# badge_Rev_B.net
KiCad netlist of a schematic drawn in EAGLE
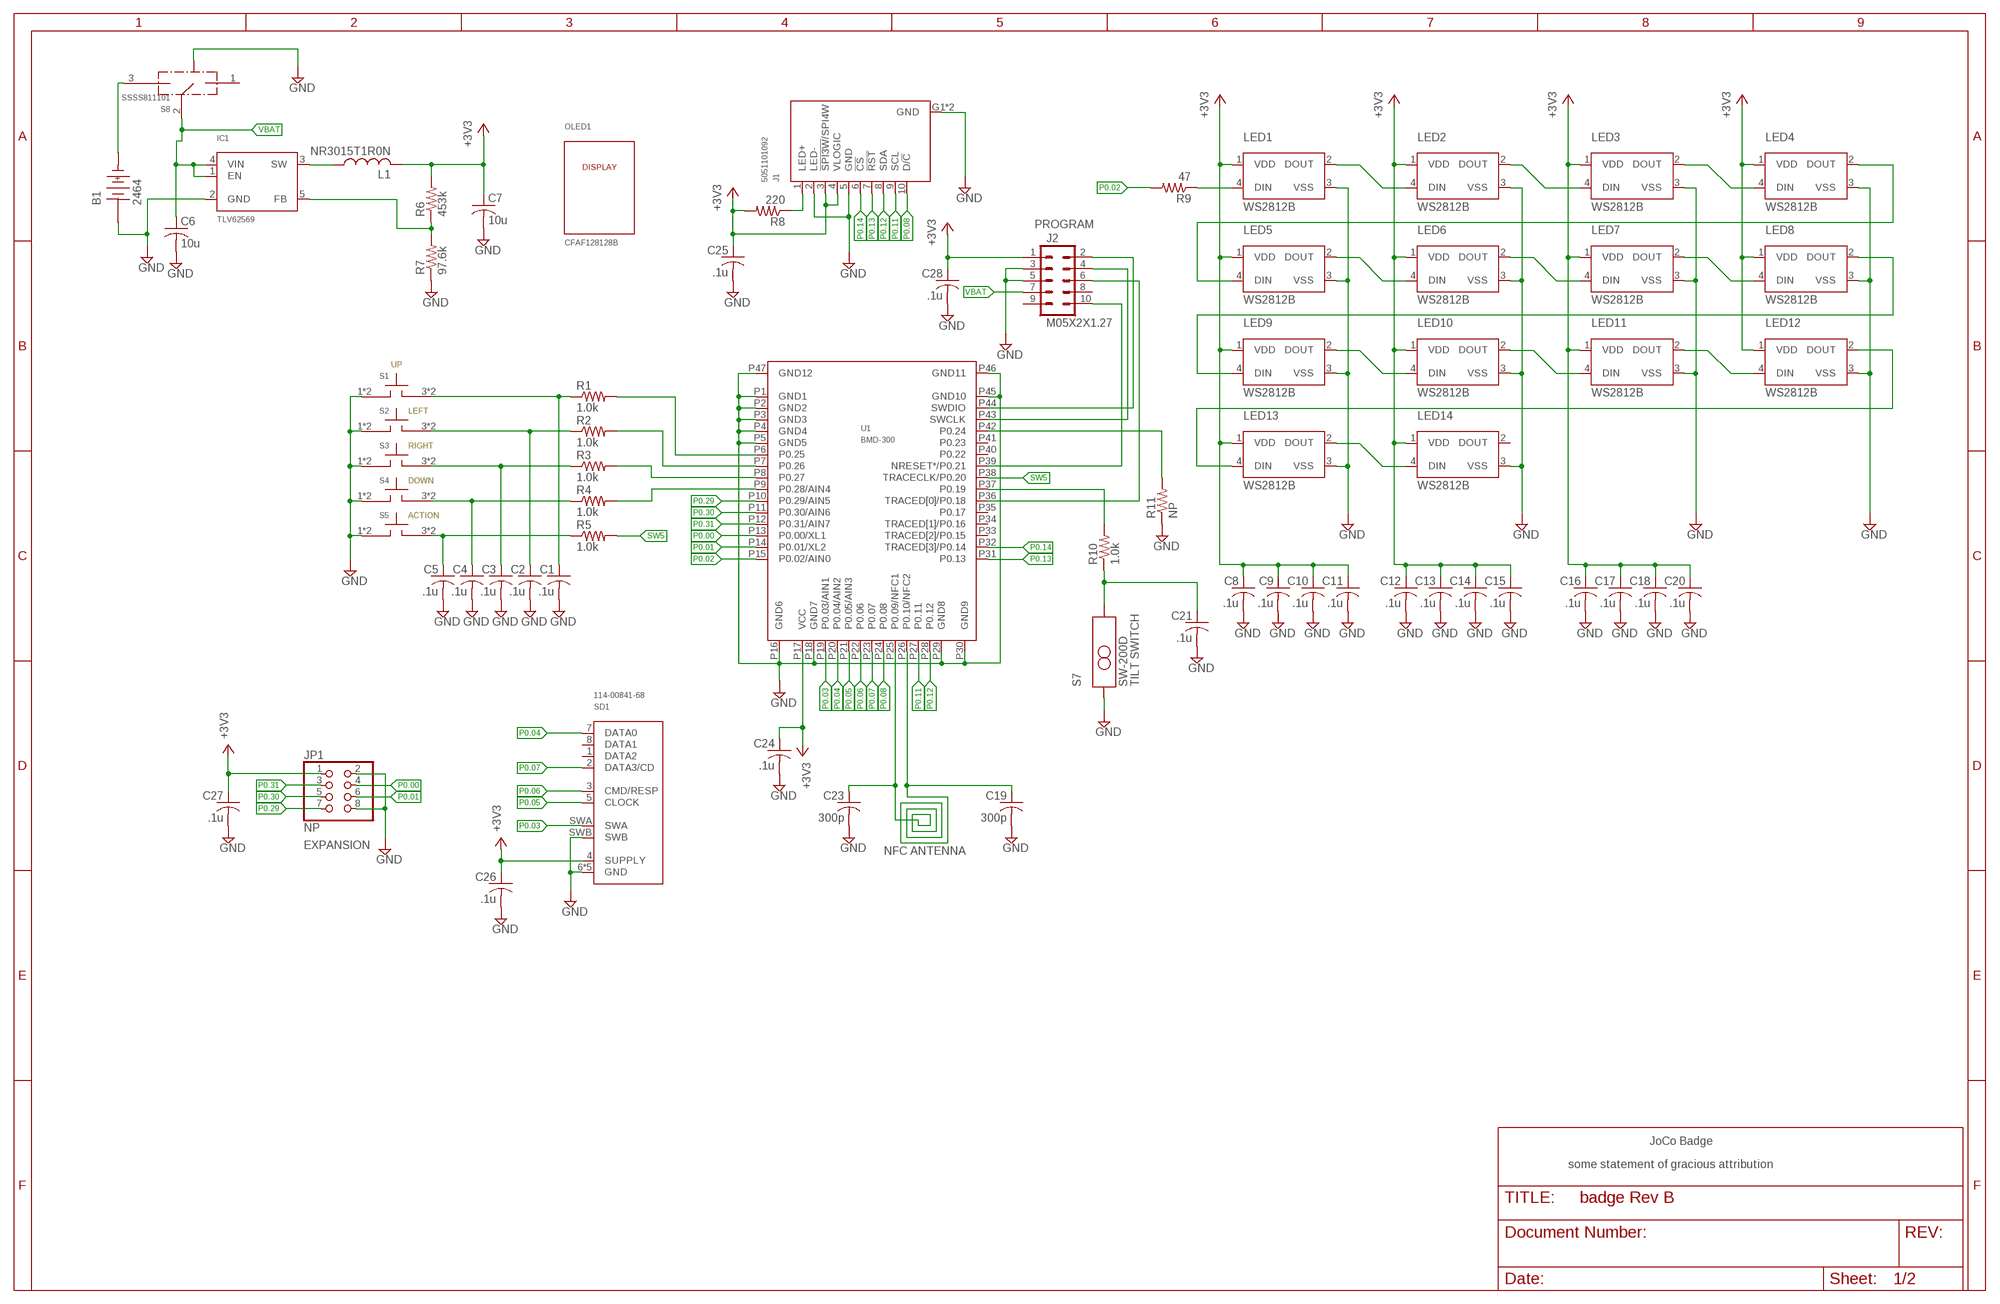
[diagram p0: schematic, sheet 1]
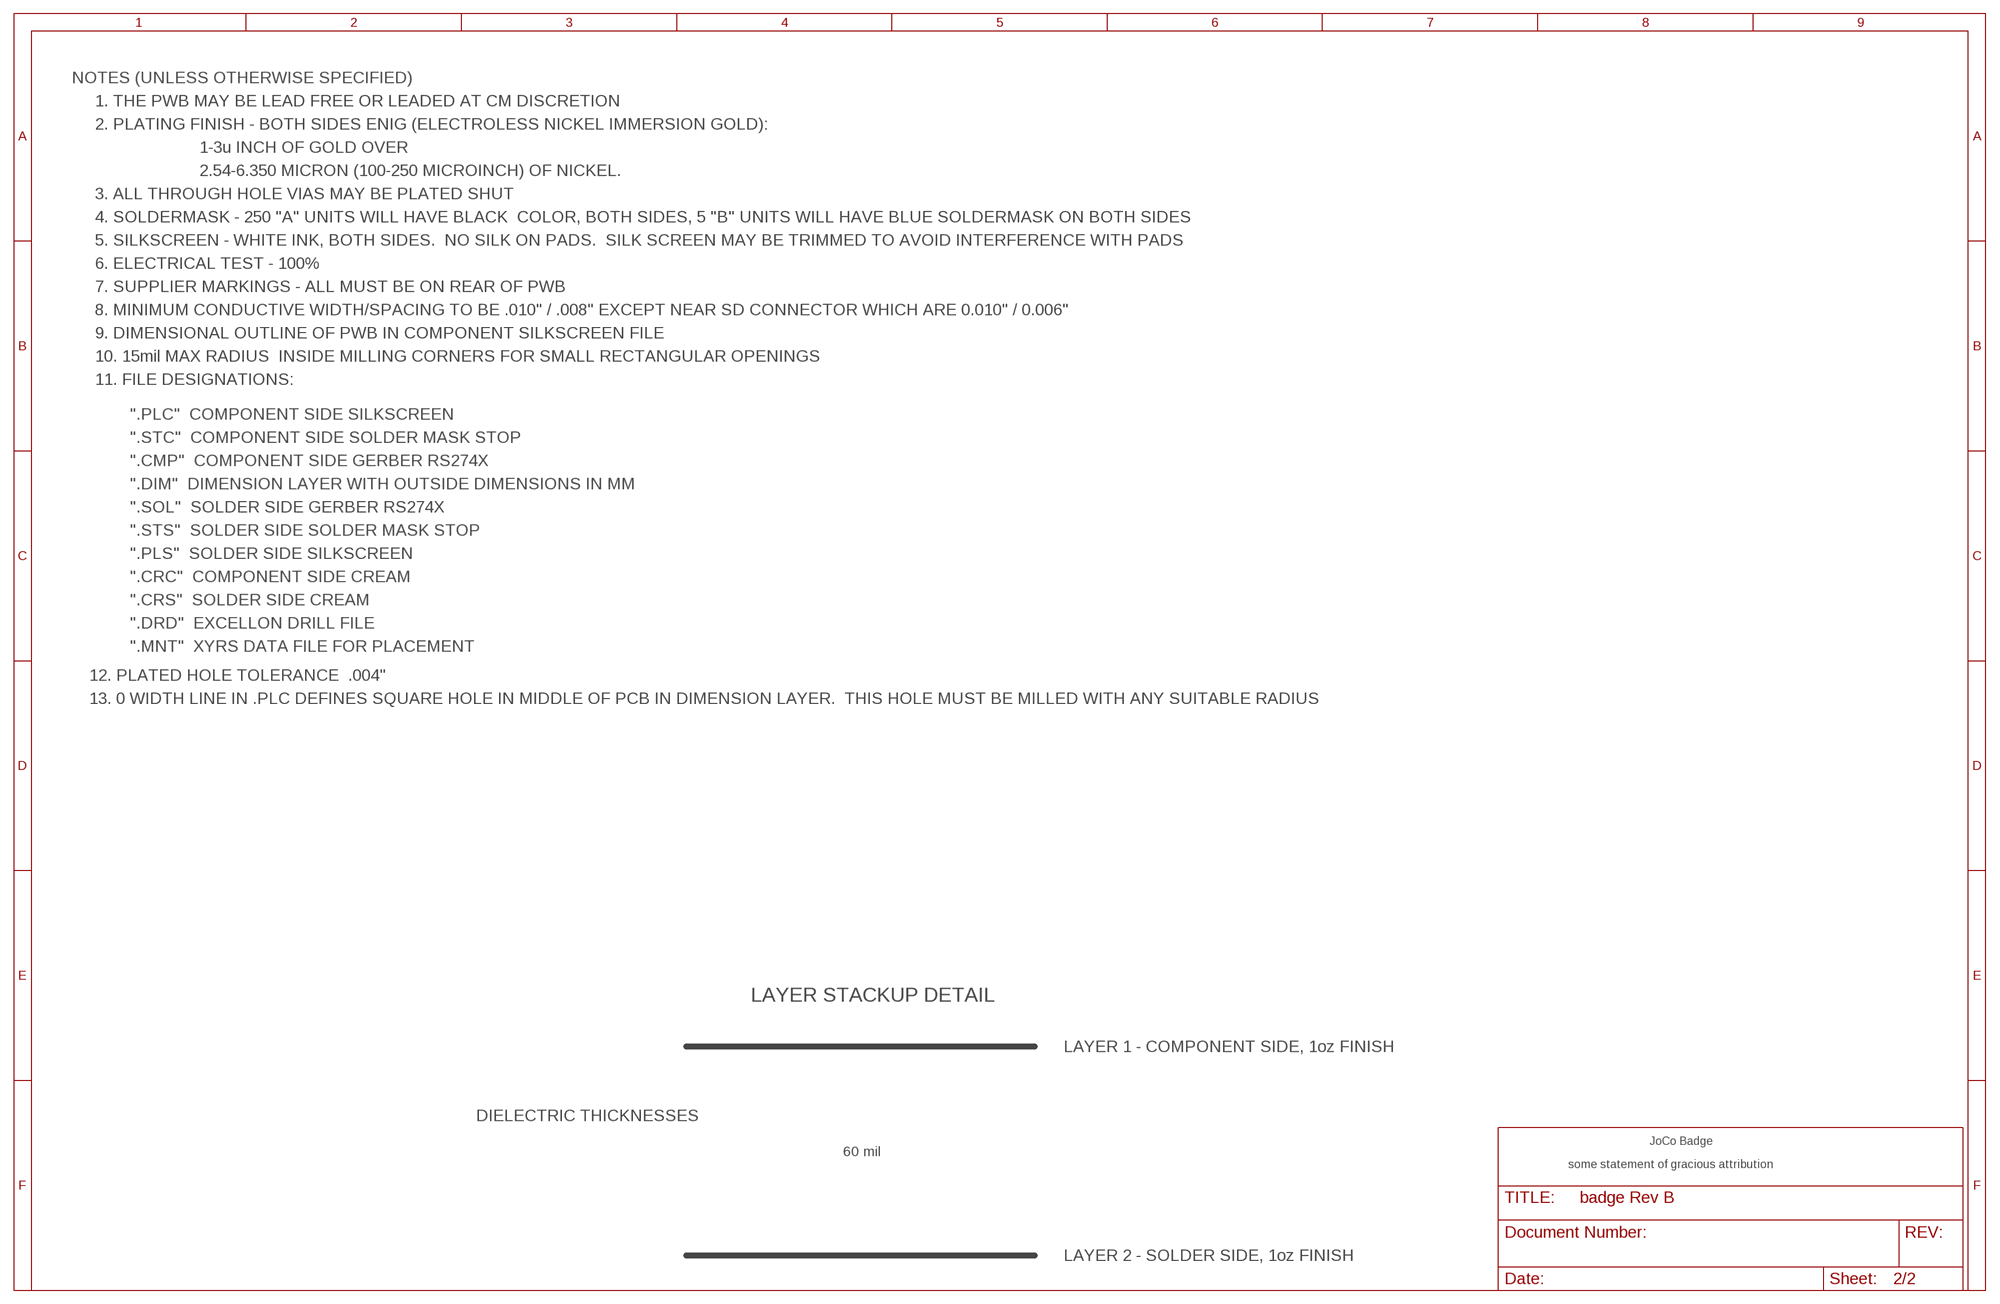
[diagram p1: schematic, sheet 2]

(export (version "E")
  (design (tool "Eeschema 10.0.6"))
  (components
    (comp (ref "B1")
      (value "2464")
      (footprint "eagle-import:2464")
      (libsource (lib "eagle-import") (part "2464"))
    )
    (comp (ref "C1")
      (value ".1u")
      (footprint "eagle-import:C0402K")
      (libsource (lib "eagle-import") (part "C-USC0402K"))
    )
    (comp (ref "C2")
      (value ".1u")
      (footprint "eagle-import:C0402K")
      (libsource (lib "eagle-import") (part "C-USC0402K"))
    )
    (comp (ref "C3")
      (value ".1u")
      (footprint "eagle-import:C0402K")
      (libsource (lib "eagle-import") (part "C-USC0402K"))
    )
    (comp (ref "C4")
      (value ".1u")
      (footprint "eagle-import:C0402K")
      (libsource (lib "eagle-import") (part "C-USC0402K"))
    )
    (comp (ref "C5")
      (value ".1u")
      (footprint "eagle-import:C0402K")
      (libsource (lib "eagle-import") (part "C-USC0402K"))
    )
    (comp (ref "C6")
      (value "10u")
      (footprint "eagle-import:C0805K")
      (fields (field (name "MPN") "JMK212BJ106KD-T"))
      (libsource (lib "eagle-import") (part "C-USC0805K"))
    )
    (comp (ref "C7")
      (value "10u")
      (footprint "eagle-import:C0805K")
      (fields (field (name "MPN") "JMK212BJ106KD-T"))
      (libsource (lib "eagle-import") (part "C-USC0805K"))
    )
    (comp (ref "C8")
      (value ".1u")
      (footprint "eagle-import:C0402K")
      (libsource (lib "eagle-import") (part "C-USC0402K"))
    )
    (comp (ref "C9")
      (value ".1u")
      (footprint "eagle-import:C0402K")
      (libsource (lib "eagle-import") (part "C-USC0402K"))
    )
    (comp (ref "C10")
      (value ".1u")
      (footprint "eagle-import:C0402K")
      (libsource (lib "eagle-import") (part "C-USC0402K"))
    )
    (comp (ref "C11")
      (value ".1u")
      (footprint "eagle-import:C0402K")
      (libsource (lib "eagle-import") (part "C-USC0402K"))
    )
    (comp (ref "C12")
      (value ".1u")
      (footprint "eagle-import:C0402K")
      (libsource (lib "eagle-import") (part "C-USC0402K"))
    )
    (comp (ref "C13")
      (value ".1u")
      (footprint "eagle-import:C0402K")
      (libsource (lib "eagle-import") (part "C-USC0402K"))
    )
    (comp (ref "C14")
      (value ".1u")
      (footprint "eagle-import:C0402K")
      (libsource (lib "eagle-import") (part "C-USC0402K"))
    )
    (comp (ref "C15")
      (value ".1u")
      (footprint "eagle-import:C0402K")
      (libsource (lib "eagle-import") (part "C-USC0402K"))
    )
    (comp (ref "C16")
      (value ".1u")
      (footprint "eagle-import:C0402K")
      (libsource (lib "eagle-import") (part "C-USC0402K"))
    )
    (comp (ref "C17")
      (value ".1u")
      (footprint "eagle-import:C0402K")
      (libsource (lib "eagle-import") (part "C-USC0402K"))
    )
    (comp (ref "C18")
      (value ".1u")
      (footprint "eagle-import:C0402K")
      (libsource (lib "eagle-import") (part "C-USC0402K"))
    )
    (comp (ref "C19")
      (value "300p")
      (footprint "eagle-import:C0603K")
      (libsource (lib "eagle-import") (part "C-USC0603K"))
    )
    (comp (ref "C20")
      (value ".1u")
      (footprint "eagle-import:C0402K")
      (libsource (lib "eagle-import") (part "C-USC0402K"))
    )
    (comp (ref "C21")
      (value ".1u")
      (footprint "eagle-import:C0402K")
      (libsource (lib "eagle-import") (part "C-USC0402K"))
    )
    (comp (ref "C23")
      (value "300p")
      (footprint "eagle-import:C0603K")
      (libsource (lib "eagle-import") (part "C-USC0603K"))
    )
    (comp (ref "C24")
      (value ".1u")
      (footprint "eagle-import:C0402K")
      (libsource (lib "eagle-import") (part "C-USC0402K"))
    )
    (comp (ref "C25")
      (value ".1u")
      (footprint "eagle-import:C0402K")
      (libsource (lib "eagle-import") (part "C-USC0402K"))
    )
    (comp (ref "C26")
      (value ".1u")
      (footprint "eagle-import:C0402K")
      (libsource (lib "eagle-import") (part "C-USC0402K"))
    )
    (comp (ref "C27")
      (value ".1u")
      (footprint "eagle-import:C0402K")
      (libsource (lib "eagle-import") (part "C-USC0402K"))
    )
    (comp (ref "C28")
      (value ".1u")
      (footprint "eagle-import:C0402K")
      (libsource (lib "eagle-import") (part "C-USC0402K"))
    )
    (comp (ref "IC1")
      (value "TLV62569")
      (footprint "eagle-import:DBV-5")
      (libsource (lib "eagle-import") (part "TLV62569"))
    )
    (comp (ref "J1")
      (value "5051101092")
      (footprint "eagle-import:5051101092")
      (libsource (lib "eagle-import") (part "5051101092"))
    )
    (comp (ref "J2")
      (value "M05X2X1.27")
      (footprint "eagle-import:2X5X1.27")
      (libsource (lib "eagle-import") (part "M05X2X1.27"))
    )
    (comp (ref "JP1")
      (value "NP")
      (footprint "eagle-import:2X04")
      (libsource (lib "eagle-import") (part "PINHD-2X4"))
    )
    (comp (ref "L1")
      (value "NR3015T1R0N")
      (footprint "eagle-import:NR3015")
      (libsource (lib "eagle-import") (part "NR3015"))
    )
    (comp (ref "LED1")
      (value "WS2812B")
      (footprint "eagle-import:WS2812B")
      (libsource (lib "eagle-import") (part "WS2812B"))
    )
    (comp (ref "LED2")
      (value "WS2812B")
      (footprint "eagle-import:WS2812B")
      (libsource (lib "eagle-import") (part "WS2812B"))
    )
    (comp (ref "LED3")
      (value "WS2812B")
      (footprint "eagle-import:WS2812B")
      (libsource (lib "eagle-import") (part "WS2812B"))
    )
    (comp (ref "LED4")
      (value "WS2812B")
      (footprint "eagle-import:WS2812B")
      (libsource (lib "eagle-import") (part "WS2812B"))
    )
    (comp (ref "LED5")
      (value "WS2812B")
      (footprint "eagle-import:WS2812B")
      (libsource (lib "eagle-import") (part "WS2812B"))
    )
    (comp (ref "LED6")
      (value "WS2812B")
      (footprint "eagle-import:WS2812B")
      (libsource (lib "eagle-import") (part "WS2812B"))
    )
    (comp (ref "LED7")
      (value "WS2812B")
      (footprint "eagle-import:WS2812B")
      (libsource (lib "eagle-import") (part "WS2812B"))
    )
    (comp (ref "LED8")
      (value "WS2812B")
      (footprint "eagle-import:WS2812B")
      (libsource (lib "eagle-import") (part "WS2812B"))
    )
    (comp (ref "LED9")
      (value "WS2812B")
      (footprint "eagle-import:WS2812B")
      (libsource (lib "eagle-import") (part "WS2812B"))
    )
    (comp (ref "LED10")
      (value "WS2812B")
      (footprint "eagle-import:WS2812B")
      (libsource (lib "eagle-import") (part "WS2812B"))
    )
    (comp (ref "LED11")
      (value "WS2812B")
      (footprint "eagle-import:WS2812B")
      (libsource (lib "eagle-import") (part "WS2812B"))
    )
    (comp (ref "LED12")
      (value "WS2812B")
      (footprint "eagle-import:WS2812B")
      (libsource (lib "eagle-import") (part "WS2812B"))
    )
    (comp (ref "LED13")
      (value "WS2812B")
      (footprint "eagle-import:WS2812B")
      (libsource (lib "eagle-import") (part "WS2812B"))
    )
    (comp (ref "LED14")
      (value "WS2812B")
      (footprint "eagle-import:WS2812B")
      (libsource (lib "eagle-import") (part "WS2812B"))
    )
    (comp (ref "OLED1")
      (value "CFAF128128B")
      (footprint "eagle-import:CFAF128128B")
      (libsource (lib "eagle-import") (part "CFAF128128B"))
    )
    (comp (ref "R1")
      (value "1.0k")
      (footprint "eagle-import:R0603")
      (libsource (lib "eagle-import") (part "R-US_R0603"))
    )
    (comp (ref "R2")
      (value "1.0k")
      (footprint "eagle-import:R0603")
      (libsource (lib "eagle-import") (part "R-US_R0603"))
    )
    (comp (ref "R3")
      (value "1.0k")
      (footprint "eagle-import:R0603")
      (libsource (lib "eagle-import") (part "R-US_R0603"))
    )
    (comp (ref "R4")
      (value "1.0k")
      (footprint "eagle-import:R0603")
      (libsource (lib "eagle-import") (part "R-US_R0603"))
    )
    (comp (ref "R5")
      (value "1.0k")
      (footprint "eagle-import:R0603")
      (libsource (lib "eagle-import") (part "R-US_R0603"))
    )
    (comp (ref "R6")
      (value "453k")
      (footprint "eagle-import:R0603")
      (libsource (lib "eagle-import") (part "R-US_R0603"))
    )
    (comp (ref "R7")
      (value "97.6k")
      (footprint "eagle-import:R0603")
      (libsource (lib "eagle-import") (part "R-US_R0603"))
    )
    (comp (ref "R8")
      (value "220")
      (footprint "eagle-import:R0603")
      (libsource (lib "eagle-import") (part "R-US_R0603"))
    )
    (comp (ref "R9")
      (value "47")
      (footprint "eagle-import:R0603")
      (libsource (lib "eagle-import") (part "R-US_R0603"))
    )
    (comp (ref "R10")
      (value "1.0k")
      (footprint "eagle-import:R0603")
      (libsource (lib "eagle-import") (part "R-US_R0603"))
    )
    (comp (ref "R11")
      (value "NP")
      (footprint "eagle-import:R0805")
      (libsource (lib "eagle-import") (part "R-US_R0805"))
    )
    (comp (ref "S1")
      (value "PTS810")
      (footprint "eagle-import:PTS810")
      (libsource (lib "eagle-import") (part "PTS810"))
    )
    (comp (ref "S2")
      (value "PTS810")
      (footprint "eagle-import:PTS810")
      (libsource (lib "eagle-import") (part "PTS810"))
    )
    (comp (ref "S3")
      (value "PTS810")
      (footprint "eagle-import:PTS810")
      (libsource (lib "eagle-import") (part "PTS810"))
    )
    (comp (ref "S4")
      (value "PTS810")
      (footprint "eagle-import:PTS810")
      (libsource (lib "eagle-import") (part "PTS810"))
    )
    (comp (ref "S5")
      (value "PTS810")
      (footprint "eagle-import:PTS810")
      (libsource (lib "eagle-import") (part "PTS810"))
    )
    (comp (ref "S7")
      (value "SW-200D")
      (footprint "eagle-import:SW-200D")
      (libsource (lib "eagle-import") (part "SW-200D"))
    )
    (comp (ref "S8")
      (value "SSSS811101")
      (footprint "eagle-import:SSSS811101")
      (libsource (lib "eagle-import") (part "SSSS811101"))
    )
    (comp (ref "SD1")
      (value "114-00841-68")
      (footprint "eagle-import:114-00841-68")
      (libsource (lib "eagle-import") (part "114-00841-68"))
    )
    (comp (ref "U1")
      (value "BMD-300")
      (footprint "eagle-import:BMD-300")
      (libsource (lib "eagle-import") (part "BMD-300"))
    )
  )
  (nets
    (net (code "1") (name "+3V3") (class "Default")
      (node (ref "C10") (pin "1") (pinfunction "1_1") (pintype "passive"))
      (node (ref "C11") (pin "1") (pinfunction "1_1") (pintype "passive"))
      (node (ref "C12") (pin "1") (pinfunction "1_1") (pintype "passive"))
      (node (ref "C13") (pin "1") (pinfunction "1_1") (pintype "passive"))
      (node (ref "C14") (pin "1") (pinfunction "1_1") (pintype "passive"))
      (node (ref "C15") (pin "1") (pinfunction "1_1") (pintype "passive"))
      (node (ref "C16") (pin "1") (pinfunction "1_1") (pintype "passive"))
      (node (ref "C17") (pin "1") (pinfunction "1_1") (pintype "passive"))
      (node (ref "C18") (pin "1") (pinfunction "1_1") (pintype "passive"))
      (node (ref "C20") (pin "1") (pinfunction "1_1") (pintype "passive"))
      (node (ref "C24") (pin "1") (pinfunction "1_1") (pintype "passive"))
      (node (ref "C25") (pin "1") (pinfunction "1_1") (pintype "passive"))
      (node (ref "C26") (pin "1") (pinfunction "1_1") (pintype "passive"))
      (node (ref "C27") (pin "1") (pinfunction "1_1") (pintype "passive"))
      (node (ref "C28") (pin "1") (pinfunction "1_1") (pintype "passive"))
      (node (ref "C7") (pin "1") (pinfunction "1_1") (pintype "passive"))
      (node (ref "C8") (pin "1") (pinfunction "1_1") (pintype "passive"))
      (node (ref "C9") (pin "1") (pinfunction "1_1") (pintype "passive"))
      (node (ref "J1") (pin "3") (pinfunction "~{SPI3W}/SPI4W_3") (pintype "bidirectional"))
      (node (ref "J1") (pin "4") (pinfunction "VLOGIC_4") (pintype "bidirectional"))
      (node (ref "J2") (pin "1") (pinfunction "1_1") (pintype "passive"))
      (node (ref "JP1") (pin "1") (pinfunction "1_1") (pintype "passive"))
      (node (ref "L1") (pin "2") (pinfunction "2_2") (pintype "passive"))
      (node (ref "LED1") (pin "1") (pinfunction "VDD_1") (pintype "bidirectional"))
      (node (ref "LED10") (pin "1") (pinfunction "VDD_1") (pintype "bidirectional"))
      (node (ref "LED11") (pin "1") (pinfunction "VDD_1") (pintype "bidirectional"))
      (node (ref "LED12") (pin "1") (pinfunction "VDD_1") (pintype "bidirectional"))
      (node (ref "LED13") (pin "1") (pinfunction "VDD_1") (pintype "bidirectional"))
      (node (ref "LED14") (pin "1") (pinfunction "VDD_1") (pintype "bidirectional"))
      (node (ref "LED2") (pin "1") (pinfunction "VDD_1") (pintype "bidirectional"))
      (node (ref "LED3") (pin "1") (pinfunction "VDD_1") (pintype "bidirectional"))
      (node (ref "LED4") (pin "1") (pinfunction "VDD_1") (pintype "bidirectional"))
      (node (ref "LED5") (pin "1") (pinfunction "VDD_1") (pintype "bidirectional"))
      (node (ref "LED6") (pin "1") (pinfunction "VDD_1") (pintype "bidirectional"))
      (node (ref "LED7") (pin "1") (pinfunction "VDD_1") (pintype "bidirectional"))
      (node (ref "LED8") (pin "1") (pinfunction "VDD_1") (pintype "bidirectional"))
      (node (ref "LED9") (pin "1") (pinfunction "VDD_1") (pintype "bidirectional"))
      (node (ref "R6") (pin "2") (pinfunction "2_2") (pintype "passive"))
      (node (ref "R8") (pin "2") (pinfunction "2_2") (pintype "passive"))
      (node (ref "SD1") (pin "4") (pinfunction "SUPPLY_4") (pintype "bidirectional"))
      (node (ref "U1") (pin "P17") (pinfunction "VCC_P17") (pintype "bidirectional"))
    )
    (net (code "2") (name "GND") (class "Default")
      (node (ref "B1") (pin "-") (pinfunction "-_-") (pintype "bidirectional"))
      (node (ref "C1") (pin "2") (pinfunction "2_2") (pintype "passive"))
      (node (ref "C10") (pin "2") (pinfunction "2_2") (pintype "passive"))
      (node (ref "C11") (pin "2") (pinfunction "2_2") (pintype "passive"))
      (node (ref "C12") (pin "2") (pinfunction "2_2") (pintype "passive"))
      (node (ref "C13") (pin "2") (pinfunction "2_2") (pintype "passive"))
      (node (ref "C14") (pin "2") (pinfunction "2_2") (pintype "passive"))
      (node (ref "C15") (pin "2") (pinfunction "2_2") (pintype "passive"))
      (node (ref "C16") (pin "2") (pinfunction "2_2") (pintype "passive"))
      (node (ref "C17") (pin "2") (pinfunction "2_2") (pintype "passive"))
      (node (ref "C18") (pin "2") (pinfunction "2_2") (pintype "passive"))
      (node (ref "C19") (pin "2") (pinfunction "2_2") (pintype "passive"))
      (node (ref "C2") (pin "2") (pinfunction "2_2") (pintype "passive"))
      (node (ref "C20") (pin "2") (pinfunction "2_2") (pintype "passive"))
      (node (ref "C21") (pin "2") (pinfunction "2_2") (pintype "passive"))
      (node (ref "C23") (pin "2") (pinfunction "2_2") (pintype "passive"))
      (node (ref "C24") (pin "2") (pinfunction "2_2") (pintype "passive"))
      (node (ref "C25") (pin "2") (pinfunction "2_2") (pintype "passive"))
      (node (ref "C26") (pin "2") (pinfunction "2_2") (pintype "passive"))
      (node (ref "C27") (pin "2") (pinfunction "2_2") (pintype "passive"))
      (node (ref "C28") (pin "2") (pinfunction "2_2") (pintype "passive"))
      (node (ref "C3") (pin "2") (pinfunction "2_2") (pintype "passive"))
      (node (ref "C4") (pin "2") (pinfunction "2_2") (pintype "passive"))
      (node (ref "C5") (pin "2") (pinfunction "2_2") (pintype "passive"))
      (node (ref "C6") (pin "2") (pinfunction "2_2") (pintype "passive"))
      (node (ref "C7") (pin "2") (pinfunction "2_2") (pintype "passive"))
      (node (ref "C8") (pin "2") (pinfunction "2_2") (pintype "passive"))
      (node (ref "C9") (pin "2") (pinfunction "2_2") (pintype "passive"))
      (node (ref "IC1") (pin "2") (pinfunction "GND_2") (pintype "bidirectional"))
      (node (ref "J1") (pin "2") (pinfunction "LED-_2") (pintype "bidirectional"))
      (node (ref "J1") (pin "5") (pinfunction "GND_5") (pintype "bidirectional"))
      (node (ref "J1") (pin "G1") (pinfunction "GND_G1") (pintype "bidirectional"))
      (node (ref "J1") (pin "G2") (pinfunction "GND_G2") (pintype "bidirectional"))
      (node (ref "J2") (pin "3") (pinfunction "3_3") (pintype "passive"))
      (node (ref "J2") (pin "5") (pinfunction "5_5") (pintype "passive"))
      (node (ref "JP1") (pin "2") (pinfunction "2_2") (pintype "passive"))
      (node (ref "JP1") (pin "8") (pinfunction "8_8") (pintype "passive"))
      (node (ref "LED1") (pin "3") (pinfunction "VSS_3") (pintype "bidirectional"))
      (node (ref "LED10") (pin "3") (pinfunction "VSS_3") (pintype "bidirectional"))
      (node (ref "LED11") (pin "3") (pinfunction "VSS_3") (pintype "bidirectional"))
      (node (ref "LED12") (pin "3") (pinfunction "VSS_3") (pintype "bidirectional"))
      (node (ref "LED13") (pin "3") (pinfunction "VSS_3") (pintype "bidirectional"))
      (node (ref "LED14") (pin "3") (pinfunction "VSS_3") (pintype "bidirectional"))
      (node (ref "LED2") (pin "3") (pinfunction "VSS_3") (pintype "bidirectional"))
      (node (ref "LED3") (pin "3") (pinfunction "VSS_3") (pintype "bidirectional"))
      (node (ref "LED4") (pin "3") (pinfunction "VSS_3") (pintype "bidirectional"))
      (node (ref "LED5") (pin "3") (pinfunction "VSS_3") (pintype "bidirectional"))
      (node (ref "LED6") (pin "3") (pinfunction "VSS_3") (pintype "bidirectional"))
      (node (ref "LED7") (pin "3") (pinfunction "VSS_3") (pintype "bidirectional"))
      (node (ref "LED8") (pin "3") (pinfunction "VSS_3") (pintype "bidirectional"))
      (node (ref "LED9") (pin "3") (pinfunction "VSS_3") (pintype "bidirectional"))
      (node (ref "R11") (pin "1") (pinfunction "1_1") (pintype "passive"))
      (node (ref "R7") (pin "1") (pinfunction "1_1") (pintype "passive"))
      (node (ref "S1") (pin "1") (pinfunction "A_1") (pintype "bidirectional"))
      (node (ref "S1") (pin "2") (pinfunction "A_2") (pintype "bidirectional"))
      (node (ref "S2") (pin "1") (pinfunction "A_1") (pintype "bidirectional"))
      (node (ref "S2") (pin "2") (pinfunction "A_2") (pintype "bidirectional"))
      (node (ref "S3") (pin "1") (pinfunction "A_1") (pintype "bidirectional"))
      (node (ref "S3") (pin "2") (pinfunction "A_2") (pintype "bidirectional"))
      (node (ref "S4") (pin "1") (pinfunction "A_1") (pintype "bidirectional"))
      (node (ref "S4") (pin "2") (pinfunction "A_2") (pintype "bidirectional"))
      (node (ref "S5") (pin "1") (pinfunction "A_1") (pintype "bidirectional"))
      (node (ref "S5") (pin "2") (pinfunction "A_2") (pintype "bidirectional"))
      (node (ref "S7") (pin "A") (pinfunction "P$1_A") (pintype "bidirectional"))
      (node (ref "S8") (pin "G1") (pinfunction "GND_G1") (pintype "bidirectional"))
      (node (ref "S8") (pin "G2") (pinfunction "GND_G2") (pintype "bidirectional"))
      (node (ref "S8") (pin "G3") (pinfunction "GND_G3") (pintype "bidirectional"))
      (node (ref "S8") (pin "G4") (pinfunction "GND_G4") (pintype "bidirectional"))
      (node (ref "SD1") (pin "6") (pinfunction "GND_6") (pintype "bidirectional"))
      (node (ref "SD1") (pin "G1") (pinfunction "GND_G1") (pintype "bidirectional"))
      (node (ref "SD1") (pin "G2") (pinfunction "GND_G2") (pintype "bidirectional"))
      (node (ref "SD1") (pin "G3") (pinfunction "GND_G3") (pintype "bidirectional"))
      (node (ref "SD1") (pin "G4") (pinfunction "GND_G4") (pintype "bidirectional"))
      (node (ref "SD1") (pin "SWB") (pinfunction "SWB_SWB") (pintype "bidirectional"))
      (node (ref "U1") (pin "P1") (pinfunction "GND1_P1") (pintype "bidirectional"))
      (node (ref "U1") (pin "P16") (pinfunction "GND6_P16") (pintype "bidirectional"))
      (node (ref "U1") (pin "P18") (pinfunction "GND7_P18") (pintype "bidirectional"))
      (node (ref "U1") (pin "P2") (pinfunction "GND2_P2") (pintype "bidirectional"))
      (node (ref "U1") (pin "P29") (pinfunction "GND8_P29") (pintype "bidirectional"))
      (node (ref "U1") (pin "P3") (pinfunction "GND3_P3") (pintype "bidirectional"))
      (node (ref "U1") (pin "P30") (pinfunction "GND9_P30") (pintype "bidirectional"))
      (node (ref "U1") (pin "P4") (pinfunction "GND4_P4") (pintype "bidirectional"))
      (node (ref "U1") (pin "P45") (pinfunction "GND10_P45") (pintype "bidirectional"))
      (node (ref "U1") (pin "P46") (pinfunction "GND11_P46") (pintype "bidirectional"))
      (node (ref "U1") (pin "P47") (pinfunction "GND12_P47") (pintype "bidirectional"))
      (node (ref "U1") (pin "P5") (pinfunction "GND5_P5") (pintype "bidirectional"))
    )
    (net (code "3") (name "Net-(B1-Pad+)") (class "Default")
      (node (ref "B1") (pin "+") (pinfunction "+_+") (pintype "bidirectional"))
      (node (ref "S8") (pin "3") (pinfunction "3_3") (pintype "bidirectional"))
    )
    (net (code "4") (name "Net-(C1-Pad1)") (class "Default")
      (node (ref "C1") (pin "1") (pinfunction "1_1") (pintype "passive"))
      (node (ref "R1") (pin "1") (pinfunction "1_1") (pintype "passive"))
      (node (ref "S1") (pin "3") (pinfunction "B_3") (pintype "bidirectional"))
      (node (ref "S1") (pin "4") (pinfunction "B_4") (pintype "bidirectional"))
    )
    (net (code "5") (name "Net-(C2-Pad1)") (class "Default")
      (node (ref "C2") (pin "1") (pinfunction "1_1") (pintype "passive"))
      (node (ref "R2") (pin "1") (pinfunction "1_1") (pintype "passive"))
      (node (ref "S2") (pin "3") (pinfunction "B_3") (pintype "bidirectional"))
      (node (ref "S2") (pin "4") (pinfunction "B_4") (pintype "bidirectional"))
    )
    (net (code "6") (name "Net-(C3-Pad1)") (class "Default")
      (node (ref "C3") (pin "1") (pinfunction "1_1") (pintype "passive"))
      (node (ref "R3") (pin "1") (pinfunction "1_1") (pintype "passive"))
      (node (ref "S3") (pin "3") (pinfunction "B_3") (pintype "bidirectional"))
      (node (ref "S3") (pin "4") (pinfunction "B_4") (pintype "bidirectional"))
    )
    (net (code "7") (name "Net-(C4-Pad1)") (class "Default")
      (node (ref "C4") (pin "1") (pinfunction "1_1") (pintype "passive"))
      (node (ref "R4") (pin "1") (pinfunction "1_1") (pintype "passive"))
      (node (ref "S4") (pin "3") (pinfunction "B_3") (pintype "bidirectional"))
      (node (ref "S4") (pin "4") (pinfunction "B_4") (pintype "bidirectional"))
    )
    (net (code "8") (name "Net-(C5-Pad1)") (class "Default")
      (node (ref "C5") (pin "1") (pinfunction "1_1") (pintype "passive"))
      (node (ref "R5") (pin "1") (pinfunction "1_1") (pintype "passive"))
      (node (ref "S5") (pin "3") (pinfunction "B_3") (pintype "bidirectional"))
      (node (ref "S5") (pin "4") (pinfunction "B_4") (pintype "bidirectional"))
    )
    (net (code "9") (name "Net-(IC1-FB)") (class "Default")
      (node (ref "IC1") (pin "5") (pinfunction "FB_5") (pintype "bidirectional"))
      (node (ref "R6") (pin "1") (pinfunction "1_1") (pintype "passive"))
      (node (ref "R7") (pin "2") (pinfunction "2_2") (pintype "passive"))
    )
    (net (code "10") (name "Net-(IC1-SW)") (class "Default")
      (node (ref "IC1") (pin "3") (pinfunction "SW_3") (pintype "bidirectional"))
      (node (ref "L1") (pin "1") (pinfunction "1_1") (pintype "passive"))
    )
    (net (code "11") (name "Net-(J1-LED+)") (class "Default")
      (node (ref "J1") (pin "1") (pinfunction "LED+_1") (pintype "bidirectional"))
      (node (ref "R8") (pin "1") (pinfunction "1_1") (pintype "passive"))
    )
    (net (code "12") (name "Net-(LED1-DIN)") (class "Default")
      (node (ref "LED1") (pin "4") (pinfunction "DIN_4") (pintype "bidirectional"))
      (node (ref "R9") (pin "1") (pinfunction "1_1") (pintype "passive"))
    )
    (net (code "13") (name "Net-(LED1-DOUT)") (class "Default")
      (node (ref "LED1") (pin "2") (pinfunction "DOUT_2") (pintype "bidirectional"))
      (node (ref "LED2") (pin "4") (pinfunction "DIN_4") (pintype "bidirectional"))
    )
    (net (code "14") (name "Net-(LED2-DOUT)") (class "Default")
      (node (ref "LED2") (pin "2") (pinfunction "DOUT_2") (pintype "bidirectional"))
      (node (ref "LED3") (pin "4") (pinfunction "DIN_4") (pintype "bidirectional"))
    )
    (net (code "15") (name "Net-(LED3-DOUT)") (class "Default")
      (node (ref "LED3") (pin "2") (pinfunction "DOUT_2") (pintype "bidirectional"))
      (node (ref "LED4") (pin "4") (pinfunction "DIN_4") (pintype "bidirectional"))
    )
    (net (code "16") (name "Net-(LED4-DOUT)") (class "Default")
      (node (ref "LED4") (pin "2") (pinfunction "DOUT_2") (pintype "bidirectional"))
      (node (ref "LED5") (pin "4") (pinfunction "DIN_4") (pintype "bidirectional"))
    )
    (net (code "17") (name "Net-(LED5-DOUT)") (class "Default")
      (node (ref "LED5") (pin "2") (pinfunction "DOUT_2") (pintype "bidirectional"))
      (node (ref "LED6") (pin "4") (pinfunction "DIN_4") (pintype "bidirectional"))
    )
    (net (code "18") (name "Net-(LED6-DOUT)") (class "Default")
      (node (ref "LED6") (pin "2") (pinfunction "DOUT_2") (pintype "bidirectional"))
      (node (ref "LED7") (pin "4") (pinfunction "DIN_4") (pintype "bidirectional"))
    )
    (net (code "19") (name "Net-(LED7-DOUT)") (class "Default")
      (node (ref "LED7") (pin "2") (pinfunction "DOUT_2") (pintype "bidirectional"))
      (node (ref "LED8") (pin "4") (pinfunction "DIN_4") (pintype "bidirectional"))
    )
    (net (code "20") (name "Net-(LED8-DOUT)") (class "Default")
      (node (ref "LED8") (pin "2") (pinfunction "DOUT_2") (pintype "bidirectional"))
      (node (ref "LED9") (pin "4") (pinfunction "DIN_4") (pintype "bidirectional"))
    )
    (net (code "21") (name "Net-(LED10-DIN)") (class "Default")
      (node (ref "LED10") (pin "4") (pinfunction "DIN_4") (pintype "bidirectional"))
      (node (ref "LED9") (pin "2") (pinfunction "DOUT_2") (pintype "bidirectional"))
    )
    (net (code "22") (name "Net-(LED10-DOUT)") (class "Default")
      (node (ref "LED10") (pin "2") (pinfunction "DOUT_2") (pintype "bidirectional"))
      (node (ref "LED11") (pin "4") (pinfunction "DIN_4") (pintype "bidirectional"))
    )
    (net (code "23") (name "Net-(LED11-DOUT)") (class "Default")
      (node (ref "LED11") (pin "2") (pinfunction "DOUT_2") (pintype "bidirectional"))
      (node (ref "LED12") (pin "4") (pinfunction "DIN_4") (pintype "bidirectional"))
    )
    (net (code "24") (name "Net-(LED12-DOUT)") (class "Default")
      (node (ref "LED12") (pin "2") (pinfunction "DOUT_2") (pintype "bidirectional"))
      (node (ref "LED13") (pin "4") (pinfunction "DIN_4") (pintype "bidirectional"))
    )
    (net (code "25") (name "Net-(LED13-DOUT)") (class "Default")
      (node (ref "LED13") (pin "2") (pinfunction "DOUT_2") (pintype "bidirectional"))
      (node (ref "LED14") (pin "4") (pinfunction "DIN_4") (pintype "bidirectional"))
    )
    (net (code "26") (name "Net-(S7-P$2)") (class "Default")
      (node (ref "C21") (pin "1") (pinfunction "1_1") (pintype "passive"))
      (node (ref "R10") (pin "1") (pinfunction "1_1") (pintype "passive"))
      (node (ref "S7") (pin "C") (pinfunction "P$2_C") (pintype "bidirectional"))
    )
    (net (code "27") (name "Net-(U1-NRESET*{slash}P0.21)") (class "Default")
      (node (ref "J2") (pin "10") (pinfunction "10_10") (pintype "passive"))
      (node (ref "U1") (pin "P39") (pinfunction "NRESET*/P0.21_P39") (pintype "bidirectional"))
    )
    (net (code "28") (name "Net-(U1-P0.09{slash}NFC1)") (class "Default")
      (node (ref "C19") (pin "1") (pinfunction "1_1") (pintype "passive"))
      (node (ref "C23") (pin "1") (pinfunction "1_1") (pintype "passive"))
      (node (ref "U1") (pin "P25") (pinfunction "P0.09/NFC1_P25") (pintype "bidirectional"))
      (node (ref "U1") (pin "P26") (pinfunction "P0.10/NFC2_P26") (pintype "bidirectional"))
    )
    (net (code "29") (name "Net-(U1-P0.19)") (class "Default")
      (node (ref "R10") (pin "2") (pinfunction "2_2") (pintype "passive"))
      (node (ref "U1") (pin "P37") (pinfunction "P0.19_P37") (pintype "bidirectional"))
    )
    (net (code "30") (name "Net-(U1-P0.24)") (class "Default")
      (node (ref "R11") (pin "2") (pinfunction "2_2") (pintype "passive"))
      (node (ref "U1") (pin "P42") (pinfunction "P0.24_P42") (pintype "bidirectional"))
    )
    (net (code "31") (name "Net-(U1-P0.25)") (class "Default")
      (node (ref "R1") (pin "2") (pinfunction "2_2") (pintype "passive"))
      (node (ref "U1") (pin "P6") (pinfunction "P0.25_P6") (pintype "bidirectional"))
    )
    (net (code "32") (name "Net-(U1-P0.26)") (class "Default")
      (node (ref "R2") (pin "2") (pinfunction "2_2") (pintype "passive"))
      (node (ref "U1") (pin "P7") (pinfunction "P0.26_P7") (pintype "bidirectional"))
    )
    (net (code "33") (name "Net-(U1-P0.27)") (class "Default")
      (node (ref "R3") (pin "2") (pinfunction "2_2") (pintype "passive"))
      (node (ref "U1") (pin "P8") (pinfunction "P0.27_P8") (pintype "bidirectional"))
    )
    (net (code "34") (name "Net-(U1-P0.28{slash}AIN4)") (class "Default")
      (node (ref "R4") (pin "2") (pinfunction "2_2") (pintype "passive"))
      (node (ref "U1") (pin "P9") (pinfunction "P0.28/AIN4_P9") (pintype "bidirectional"))
    )
    (net (code "35") (name "Net-(U1-SWCLK)") (class "Default")
      (node (ref "J2") (pin "4") (pinfunction "4_4") (pintype "passive"))
      (node (ref "U1") (pin "P43") (pinfunction "SWCLK_P43") (pintype "bidirectional"))
    )
    (net (code "36") (name "Net-(U1-SWDIO)") (class "Default")
      (node (ref "J2") (pin "2") (pinfunction "2_2") (pintype "passive"))
      (node (ref "U1") (pin "P44") (pinfunction "SWDIO_P44") (pintype "bidirectional"))
    )
    (net (code "37") (name "Net-(U1-TRACED[0]{slash}P0.18)") (class "Default")
      (node (ref "J2") (pin "6") (pinfunction "6_6") (pintype "passive"))
      (node (ref "U1") (pin "P36") (pinfunction "TRACED[0]/P0.18_P36") (pintype "bidirectional"))
    )
    (net (code "38") (name "P0.00") (class "Default")
      (node (ref "JP1") (pin "4") (pinfunction "4_4") (pintype "passive"))
      (node (ref "U1") (pin "P13") (pinfunction "P0.00/XL1_P13") (pintype "bidirectional"))
    )
    (net (code "39") (name "P0.01") (class "Default")
      (node (ref "JP1") (pin "6") (pinfunction "6_6") (pintype "passive"))
      (node (ref "U1") (pin "P14") (pinfunction "P0.01/XL2_P14") (pintype "bidirectional"))
    )
    (net (code "40") (name "P0.02") (class "Default")
      (node (ref "R9") (pin "2") (pinfunction "2_2") (pintype "passive"))
      (node (ref "U1") (pin "P15") (pinfunction "P0.02/AIN0_P15") (pintype "bidirectional"))
    )
    (net (code "41") (name "P0.03") (class "Default")
      (node (ref "SD1") (pin "SWA") (pinfunction "SWA_SWA") (pintype "bidirectional"))
      (node (ref "U1") (pin "P19") (pinfunction "P0.03/AIN1_P19") (pintype "bidirectional"))
    )
    (net (code "42") (name "P0.04") (class "Default")
      (node (ref "SD1") (pin "7") (pinfunction "DATA0_7") (pintype "bidirectional"))
      (node (ref "U1") (pin "P20") (pinfunction "P0.04/AIN2_P20") (pintype "bidirectional"))
    )
    (net (code "43") (name "P0.05") (class "Default")
      (node (ref "SD1") (pin "5") (pinfunction "CLOCK_5") (pintype "bidirectional"))
      (node (ref "U1") (pin "P21") (pinfunction "P0.05/AIN3_P21") (pintype "bidirectional"))
    )
    (net (code "44") (name "P0.06") (class "Default")
      (node (ref "SD1") (pin "3") (pinfunction "CMD/RESP_3") (pintype "bidirectional"))
      (node (ref "U1") (pin "P22") (pinfunction "P0.06_P22") (pintype "bidirectional"))
    )
    (net (code "45") (name "P0.07") (class "Default")
      (node (ref "SD1") (pin "2") (pinfunction "DATA3/CD_2") (pintype "bidirectional"))
      (node (ref "U1") (pin "P23") (pinfunction "P0.07_P23") (pintype "bidirectional"))
    )
    (net (code "46") (name "P0.08") (class "Default")
      (node (ref "J1") (pin "10") (pinfunction "D/~{C}_10") (pintype "bidirectional"))
      (node (ref "U1") (pin "P24") (pinfunction "P0.08_P24") (pintype "bidirectional"))
    )
    (net (code "47") (name "P0.11") (class "Default")
      (node (ref "J1") (pin "9") (pinfunction "SCL_9") (pintype "bidirectional"))
      (node (ref "U1") (pin "P27") (pinfunction "P0.11_P27") (pintype "bidirectional"))
    )
    (net (code "48") (name "P0.12") (class "Default")
      (node (ref "J1") (pin "8") (pinfunction "SDA_8") (pintype "bidirectional"))
      (node (ref "U1") (pin "P28") (pinfunction "P0.12_P28") (pintype "bidirectional"))
    )
    (net (code "49") (name "P0.13") (class "Default")
      (node (ref "J1") (pin "7") (pinfunction "~{RST}_7") (pintype "bidirectional"))
      (node (ref "U1") (pin "P31") (pinfunction "P0.13_P31") (pintype "bidirectional"))
    )
    (net (code "50") (name "P0.14") (class "Default")
      (node (ref "J1") (pin "6") (pinfunction "~{CS}_6") (pintype "bidirectional"))
      (node (ref "U1") (pin "P32") (pinfunction "TRACED[3]/P0.14_P32") (pintype "bidirectional"))
    )
    (net (code "51") (name "P0.29") (class "Default")
      (node (ref "JP1") (pin "7") (pinfunction "7_7") (pintype "passive"))
      (node (ref "U1") (pin "P10") (pinfunction "P0.29/AIN5_P10") (pintype "bidirectional"))
    )
    (net (code "52") (name "P0.30") (class "Default")
      (node (ref "JP1") (pin "5") (pinfunction "5_5") (pintype "passive"))
      (node (ref "U1") (pin "P11") (pinfunction "P0.30/AIN6_P11") (pintype "bidirectional"))
    )
    (net (code "53") (name "P0.31") (class "Default")
      (node (ref "JP1") (pin "3") (pinfunction "3_3") (pintype "passive"))
      (node (ref "U1") (pin "P12") (pinfunction "P0.31/AIN7_P12") (pintype "bidirectional"))
    )
    (net (code "54") (name "SW5") (class "Default")
      (node (ref "R5") (pin "2") (pinfunction "2_2") (pintype "passive"))
      (node (ref "U1") (pin "P38") (pinfunction "TRACECLK/P0.20_P38") (pintype "bidirectional"))
    )
    (net (code "55") (name "VBAT") (class "Default")
      (node (ref "C6") (pin "1") (pinfunction "1_1") (pintype "passive"))
      (node (ref "IC1") (pin "1") (pinfunction "EN_1") (pintype "bidirectional"))
      (node (ref "IC1") (pin "4") (pinfunction "VIN_4") (pintype "bidirectional"))
      (node (ref "J2") (pin "7") (pinfunction "7_7") (pintype "passive"))
      (node (ref "S8") (pin "2") (pinfunction "2_2") (pintype "bidirectional"))
    )
    (net (code "56") (name "unconnected-(J2-Pad8)") (class "Default")
      (node (ref "J2") (pin "8") (pinfunction "8_8") (pintype "passive"))
    )
    (net (code "57") (name "unconnected-(J2-Pad9)") (class "Default")
      (node (ref "J2") (pin "9") (pinfunction "9_9") (pintype "passive"))
    )
    (net (code "58") (name "unconnected-(LED14-DOUT-Pad2)") (class "Default")
      (node (ref "LED14") (pin "2") (pinfunction "DOUT_2") (pintype "bidirectional"))
    )
    (net (code "59") (name "unconnected-(S8-Pad1)") (class "Default")
      (node (ref "S8") (pin "1") (pinfunction "1_1") (pintype "bidirectional"))
    )
    (net (code "60") (name "unconnected-(SD1-DATA1-Pad8)") (class "Default")
      (node (ref "SD1") (pin "8") (pinfunction "DATA1_8") (pintype "bidirectional"))
    )
    (net (code "61") (name "unconnected-(SD1-DATA2-Pad1)") (class "Default")
      (node (ref "SD1") (pin "1") (pinfunction "DATA2_1") (pintype "bidirectional"))
    )
    (net (code "62") (name "unconnected-(U1-P0.17-PadP35)") (class "Default")
      (node (ref "U1") (pin "P35") (pinfunction "P0.17_P35") (pintype "bidirectional"))
    )
    (net (code "63") (name "unconnected-(U1-P0.22-PadP40)") (class "Default")
      (node (ref "U1") (pin "P40") (pinfunction "P0.22_P40") (pintype "bidirectional"))
    )
    (net (code "64") (name "unconnected-(U1-P0.23-PadP41)") (class "Default")
      (node (ref "U1") (pin "P41") (pinfunction "P0.23_P41") (pintype "bidirectional"))
    )
    (net (code "65") (name "unconnected-(U1-TRACED[1]{slash}P0.16-PadP34)") (class "Default")
      (node (ref "U1") (pin "P34") (pinfunction "TRACED[1]/P0.16_P34") (pintype "bidirectional"))
    )
    (net (code "66") (name "unconnected-(U1-TRACED[2]{slash}P0.15-PadP33)") (class "Default")
      (node (ref "U1") (pin "P33") (pinfunction "TRACED[2]/P0.15_P33") (pintype "bidirectional"))
    )
  )
)
